# maxTouch-EXT_V1.net
KiCad netlist of a schematic drawn in EAGLE
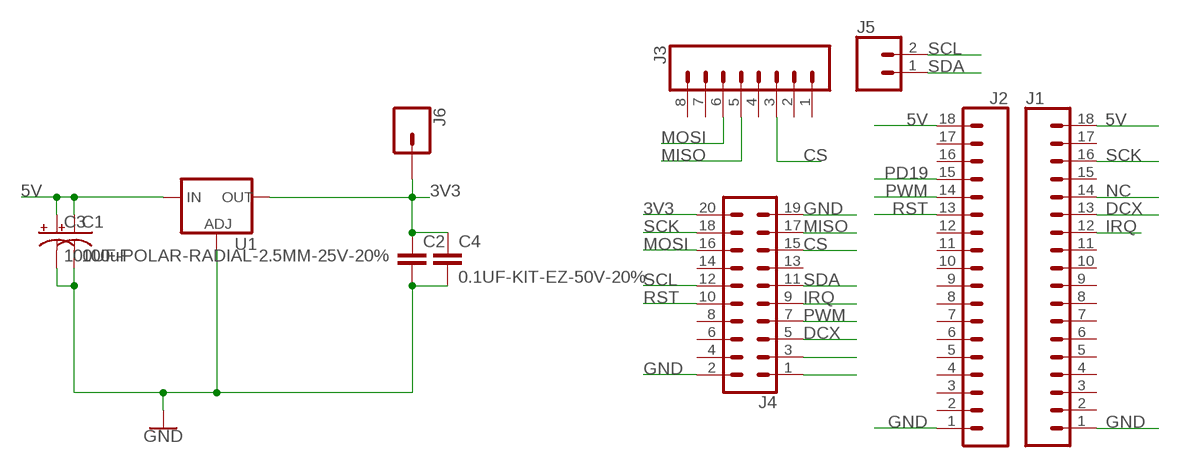
[diagram p0: schematic, sheet 1]

(export (version "E")
  (design (tool "Eeschema 10.0.6"))
  (components
    (comp (ref "C1")
      (value "100uF")
      (footprint "eagle-import:NIC_10X10.5_CAP")
      (libsource (lib "eagle-import") (part "100UF-POLAR-10X10.5-63V-20%"))
    )
    (comp (ref "C2")
      (value "10uF")
      (footprint "eagle-import:0805")
      (libsource (lib "eagle-import") (part "CAP-0805"))
    )
    (comp (ref "C3")
      (value "100UF-POLAR-RADIAL-2.5MM-25V-20%")
      (footprint "eagle-import:CPOL-RADIAL-2.5MM-6.5MM")
      (libsource (lib "eagle-import") (part "100UF-POLAR-RADIAL-2.5MM-25V-20%"))
    )
    (comp (ref "C4")
      (value "0.1UF-KIT-EZ-50V-20%")
      (footprint "eagle-import:CAP-PTH-SMALL-KIT")
      (libsource (lib "eagle-import") (part "0.1UF-KIT-EZ-50V-20%"))
    )
    (comp (ref "J1")
      (value "CONN_18SILK")
      (footprint "eagle-import:1X18")
      (libsource (lib "eagle-import") (part "CONN_18SILK"))
    )
    (comp (ref "J2")
      (value "CONN_18SILK")
      (footprint "eagle-import:1X18")
      (libsource (lib "eagle-import") (part "CONN_18SILK"))
    )
    (comp (ref "J3")
      (value "CONN_08\"")
      (footprint "eagle-import:1X08")
      (libsource (lib "eagle-import") (part "CONN_08{dblquote}"))
    )
    (comp (ref "J4")
      (value "CONN_10X2")
      (footprint "eagle-import:2X10")
      (libsource (lib "eagle-import") (part "CONN_10X2"))
    )
    (comp (ref "J5")
      (value "CONN_02")
      (footprint "eagle-import:1X02")
      (libsource (lib "eagle-import") (part "CONN_02"))
    )
    (comp (ref "J6")
      (value "CONN_01")
      (footprint "eagle-import:1X01")
      (libsource (lib "eagle-import") (part "CONN_01"))
    )
    (comp (ref "U1")
      (value "V_REG_LM1117SOT223")
      (footprint "eagle-import:SOT223")
      (libsource (lib "eagle-import") (part "V_REG_LM1117SOT223"))
    )
  )
  (nets
    (net (code "1") (name "/3V3") (class "Default")
      (node (ref "C2") (pin "1") (pinfunction "1_1") (pintype "passive"))
      (node (ref "C4") (pin "1") (pinfunction "1_1") (pintype "passive"))
      (node (ref "J4") (pin "20") (pinfunction "20_20") (pintype "passive"))
      (node (ref "J6") (pin "1") (pinfunction "1_1") (pintype "passive"))
      (node (ref "U1") (pin "2") (pinfunction "OUT_2") (pintype "output"))
      (node (ref "U1") (pin "4") (pinfunction "OUT_4") (pintype "output"))
    )
    (net (code "2") (name "/5V") (class "Default")
      (node (ref "C1") (pin "+") (pinfunction "+_+") (pintype "passive"))
      (node (ref "C3") (pin "1") (pinfunction "+_1") (pintype "passive"))
      (node (ref "J1") (pin "18") (pinfunction "18_18") (pintype "passive"))
      (node (ref "J2") (pin "18") (pinfunction "18_18") (pintype "passive"))
      (node (ref "U1") (pin "3") (pinfunction "IN_3") (pintype "input"))
    )
    (net (code "3") (name "/CS") (class "Default")
      (node (ref "J3") (pin "3") (pinfunction "3_3") (pintype "passive"))
      (node (ref "J4") (pin "15") (pinfunction "15_15") (pintype "passive"))
    )
    (net (code "4") (name "/DCX") (class "Default")
      (node (ref "J1") (pin "13") (pinfunction "13_13") (pintype "passive"))
      (node (ref "J4") (pin "5") (pinfunction "5_5") (pintype "passive"))
    )
    (net (code "5") (name "/IRQ") (class "Default")
      (node (ref "J1") (pin "12") (pinfunction "12_12") (pintype "passive"))
      (node (ref "J4") (pin "9") (pinfunction "9_9") (pintype "passive"))
    )
    (net (code "6") (name "/MISO") (class "Default")
      (node (ref "J3") (pin "5") (pinfunction "5_5") (pintype "passive"))
      (node (ref "J4") (pin "17") (pinfunction "17_17") (pintype "passive"))
    )
    (net (code "7") (name "/MOSI") (class "Default")
      (node (ref "J3") (pin "6") (pinfunction "6_6") (pintype "passive"))
      (node (ref "J4") (pin "16") (pinfunction "16_16") (pintype "passive"))
    )
    (net (code "8") (name "/NC") (class "Default")
      (node (ref "J1") (pin "14") (pinfunction "14_14") (pintype "passive"))
    )
    (net (code "9") (name "/PD19") (class "Default")
      (node (ref "J2") (pin "15") (pinfunction "15_15") (pintype "passive"))
    )
    (net (code "10") (name "/PWM") (class "Default")
      (node (ref "J2") (pin "14") (pinfunction "14_14") (pintype "passive"))
      (node (ref "J4") (pin "7") (pinfunction "7_7") (pintype "passive"))
    )
    (net (code "11") (name "/RST") (class "Default")
      (node (ref "J2") (pin "13") (pinfunction "13_13") (pintype "passive"))
      (node (ref "J4") (pin "10") (pinfunction "10_10") (pintype "passive"))
    )
    (net (code "12") (name "/SCK") (class "Default")
      (node (ref "J1") (pin "16") (pinfunction "16_16") (pintype "passive"))
      (node (ref "J4") (pin "18") (pinfunction "18_18") (pintype "passive"))
    )
    (net (code "13") (name "/SCL") (class "Default")
      (node (ref "J4") (pin "12") (pinfunction "12_12") (pintype "passive"))
      (node (ref "J5") (pin "2") (pinfunction "2_2") (pintype "passive"))
    )
    (net (code "14") (name "/SDA") (class "Default")
      (node (ref "J4") (pin "11") (pinfunction "11_11") (pintype "passive"))
      (node (ref "J5") (pin "1") (pinfunction "1_1") (pintype "passive"))
    )
    (net (code "15") (name "GND") (class "Default")
      (node (ref "C1") (pin "-") (pinfunction "-_-") (pintype "passive"))
      (node (ref "C2") (pin "2") (pinfunction "2_2") (pintype "passive"))
      (node (ref "C3") (pin "2") (pinfunction "-_2") (pintype "passive"))
      (node (ref "C4") (pin "2") (pinfunction "2_2") (pintype "passive"))
      (node (ref "J1") (pin "1") (pinfunction "1_1") (pintype "passive"))
      (node (ref "J2") (pin "1") (pinfunction "1_1") (pintype "passive"))
      (node (ref "J4") (pin "19") (pinfunction "19_19") (pintype "passive"))
      (node (ref "J4") (pin "2") (pinfunction "2_2") (pintype "passive"))
      (node (ref "U1") (pin "1") (pinfunction "ADJ_1") (pintype "input"))
    )
    (net (code "16") (name "unconnected-(J1-Pad2)") (class "Default")
      (node (ref "J1") (pin "2") (pinfunction "2_2") (pintype "passive"))
    )
    (net (code "17") (name "unconnected-(J1-Pad3)") (class "Default")
      (node (ref "J1") (pin "3") (pinfunction "3_3") (pintype "passive"))
    )
    (net (code "18") (name "unconnected-(J1-Pad4)") (class "Default")
      (node (ref "J1") (pin "4") (pinfunction "4_4") (pintype "passive"))
    )
    (net (code "19") (name "unconnected-(J1-Pad5)") (class "Default")
      (node (ref "J1") (pin "5") (pinfunction "5_5") (pintype "passive"))
    )
    (net (code "20") (name "unconnected-(J1-Pad6)") (class "Default")
      (node (ref "J1") (pin "6") (pinfunction "6_6") (pintype "passive"))
    )
    (net (code "21") (name "unconnected-(J1-Pad7)") (class "Default")
      (node (ref "J1") (pin "7") (pinfunction "7_7") (pintype "passive"))
    )
    (net (code "22") (name "unconnected-(J1-Pad8)") (class "Default")
      (node (ref "J1") (pin "8") (pinfunction "8_8") (pintype "passive"))
    )
    (net (code "23") (name "unconnected-(J1-Pad9)") (class "Default")
      (node (ref "J1") (pin "9") (pinfunction "9_9") (pintype "passive"))
    )
    (net (code "24") (name "unconnected-(J1-Pad10)") (class "Default")
      (node (ref "J1") (pin "10") (pinfunction "10_10") (pintype "passive"))
    )
    (net (code "25") (name "unconnected-(J1-Pad11)") (class "Default")
      (node (ref "J1") (pin "11") (pinfunction "11_11") (pintype "passive"))
    )
    (net (code "26") (name "unconnected-(J1-Pad15)") (class "Default")
      (node (ref "J1") (pin "15") (pinfunction "15_15") (pintype "passive"))
    )
    (net (code "27") (name "unconnected-(J1-Pad17)") (class "Default")
      (node (ref "J1") (pin "17") (pinfunction "17_17") (pintype "passive"))
    )
    (net (code "28") (name "unconnected-(J2-Pad2)") (class "Default")
      (node (ref "J2") (pin "2") (pinfunction "2_2") (pintype "passive"))
    )
    (net (code "29") (name "unconnected-(J2-Pad3)") (class "Default")
      (node (ref "J2") (pin "3") (pinfunction "3_3") (pintype "passive"))
    )
    (net (code "30") (name "unconnected-(J2-Pad4)") (class "Default")
      (node (ref "J2") (pin "4") (pinfunction "4_4") (pintype "passive"))
    )
    (net (code "31") (name "unconnected-(J2-Pad5)") (class "Default")
      (node (ref "J2") (pin "5") (pinfunction "5_5") (pintype "passive"))
    )
    (net (code "32") (name "unconnected-(J2-Pad6)") (class "Default")
      (node (ref "J2") (pin "6") (pinfunction "6_6") (pintype "passive"))
    )
    (net (code "33") (name "unconnected-(J2-Pad7)") (class "Default")
      (node (ref "J2") (pin "7") (pinfunction "7_7") (pintype "passive"))
    )
    (net (code "34") (name "unconnected-(J2-Pad8)") (class "Default")
      (node (ref "J2") (pin "8") (pinfunction "8_8") (pintype "passive"))
    )
    (net (code "35") (name "unconnected-(J2-Pad9)") (class "Default")
      (node (ref "J2") (pin "9") (pinfunction "9_9") (pintype "passive"))
    )
    (net (code "36") (name "unconnected-(J2-Pad10)") (class "Default")
      (node (ref "J2") (pin "10") (pinfunction "10_10") (pintype "passive"))
    )
    (net (code "37") (name "unconnected-(J2-Pad11)") (class "Default")
      (node (ref "J2") (pin "11") (pinfunction "11_11") (pintype "passive"))
    )
    (net (code "38") (name "unconnected-(J2-Pad12)") (class "Default")
      (node (ref "J2") (pin "12") (pinfunction "12_12") (pintype "passive"))
    )
    (net (code "39") (name "unconnected-(J2-Pad16)") (class "Default")
      (node (ref "J2") (pin "16") (pinfunction "16_16") (pintype "passive"))
    )
    (net (code "40") (name "unconnected-(J2-Pad17)") (class "Default")
      (node (ref "J2") (pin "17") (pinfunction "17_17") (pintype "passive"))
    )
    (net (code "41") (name "unconnected-(J3-Pad1)") (class "Default")
      (node (ref "J3") (pin "1") (pinfunction "1_1") (pintype "passive"))
    )
    (net (code "42") (name "unconnected-(J3-Pad2)") (class "Default")
      (node (ref "J3") (pin "2") (pinfunction "2_2") (pintype "passive"))
    )
    (net (code "43") (name "unconnected-(J3-Pad4)") (class "Default")
      (node (ref "J3") (pin "4") (pinfunction "4_4") (pintype "passive"))
    )
    (net (code "44") (name "unconnected-(J3-Pad7)") (class "Default")
      (node (ref "J3") (pin "7") (pinfunction "7_7") (pintype "passive"))
    )
    (net (code "45") (name "unconnected-(J3-Pad8)") (class "Default")
      (node (ref "J3") (pin "8") (pinfunction "8_8") (pintype "passive"))
    )
    (net (code "46") (name "unconnected-(J4-Pad1)") (class "Default")
      (node (ref "J4") (pin "1") (pinfunction "1_1") (pintype "passive"))
    )
    (net (code "47") (name "unconnected-(J4-Pad3)") (class "Default")
      (node (ref "J4") (pin "3") (pinfunction "3_3") (pintype "passive"))
    )
    (net (code "48") (name "unconnected-(J4-Pad4)") (class "Default")
      (node (ref "J4") (pin "4") (pinfunction "4_4") (pintype "passive"))
    )
    (net (code "49") (name "unconnected-(J4-Pad6)") (class "Default")
      (node (ref "J4") (pin "6") (pinfunction "6_6") (pintype "passive"))
    )
    (net (code "50") (name "unconnected-(J4-Pad8)") (class "Default")
      (node (ref "J4") (pin "8") (pinfunction "8_8") (pintype "passive"))
    )
    (net (code "51") (name "unconnected-(J4-Pad13)") (class "Default")
      (node (ref "J4") (pin "13") (pinfunction "13_13") (pintype "passive"))
    )
    (net (code "52") (name "unconnected-(J4-Pad14)") (class "Default")
      (node (ref "J4") (pin "14") (pinfunction "14_14") (pintype "passive"))
    )
  )
)
